# SCH_solar_powered_business_card.net
KiCad netlist of a schematic drawn in EasyEDA
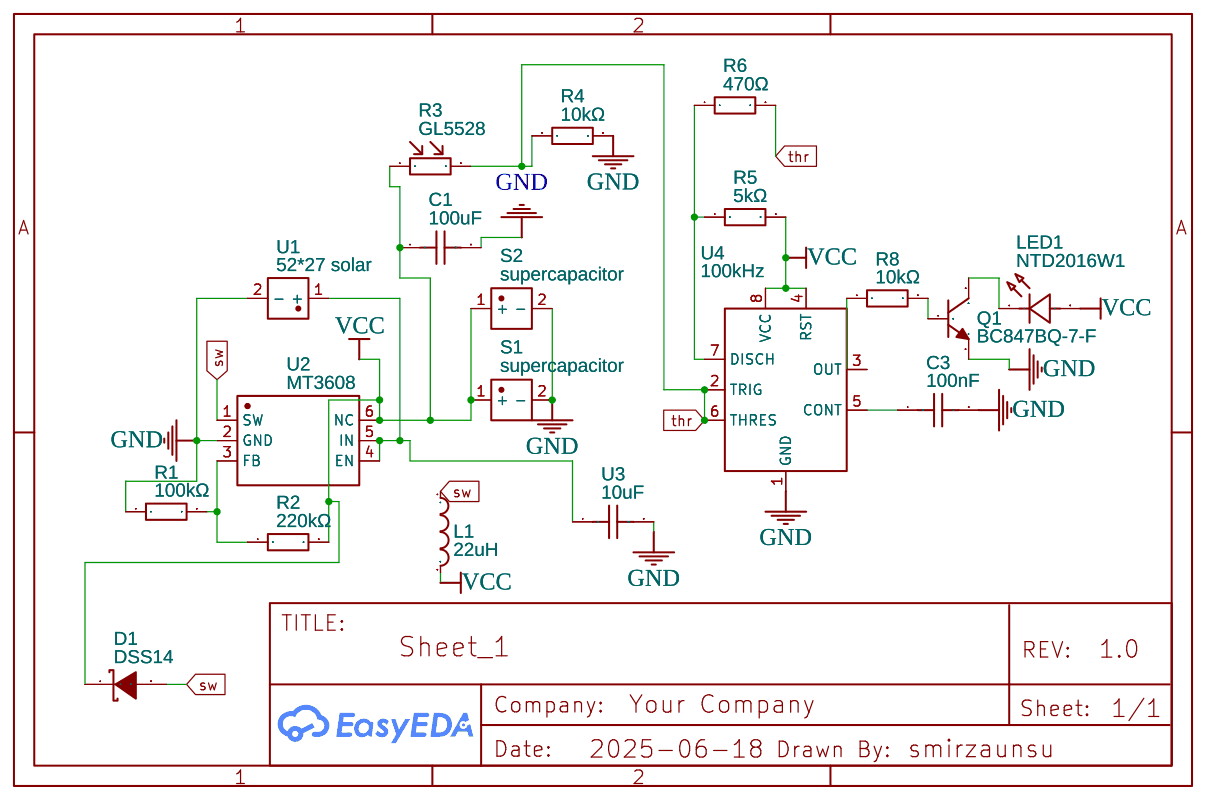
[diagram p0: schematic sheet]

(export (version "E")
  (design (tool "Eeschema 10.0.6"))
  (components
    (comp (ref "C1")
      (value "100uF")
      (fields
        (field (name "Manufacturer Part") "CGA0805X5R107M6R3MT")
        (field (name "Manufacturer") "HRE(芯声)")
      )
      (libsource (lib "") (part "CGA0805X5R107M6R3MT"))
    )
    (comp (ref "C3")
      (value "100nF")
      (fields
        (field (name "Manufacturer Part") "CGA0603X7R104K100JT")
        (field (name "Manufacturer") "HRE(芯声)")
      )
      (libsource (lib "") (part "CGA0603X7R104K100JT"))
    )
    (comp (ref "D1")
      (value "DSS14")
      (fields (field (name "Manufacturer") "星海"))
      (libsource (lib "") (part "DSS14"))
    )
    (comp (ref "L1")
      (value "22uH")
      (fields
        (field (name "Manufacturer Part") "SLD10D40S-220MTT")
        (field (name "Manufacturer") "Sunltech(韩国顺磁)")
      )
      (libsource (lib "") (part "SLD10D40S-220MTT"))
    )
    (comp (ref "LED1")
      (value "NTD2016W1")
      (fields (field (name "Manufacturer") "国星光电"))
      (libsource (lib "") (part "NTD2016W1"))
    )
    (comp (ref "Q1")
      (value "BC847BQ-7-F")
      (fields (field (name "Manufacturer") "DIODES(美台)"))
      (libsource (lib "") (part "BC847BQ-7-F"))
    )
    (comp (ref "R1")
      (value "100kΩ")
      (fields (field (name "Manufacturer Part") "RT0603DRE07100KL") (field (name "Manufacturer") "YAGEO(国巨)"))
      (libsource (lib "") (part "RT0603DRE07100KL"))
    )
    (comp (ref "R2")
      (value "220kΩ")
      (fields (field (name "Manufacturer Part") "RC0603JR-07220KL") (field (name "Manufacturer") "YAGEO(国巨)"))
      (libsource (lib "") (part "RC0603JR-07220KL"))
    )
    (comp (ref "R3")
      (value "GL5528")
      (fields (field (name "Manufacturer") "森霸"))
      (libsource (lib "") (part "GL5528"))
    )
    (comp (ref "R4")
      (value "10kΩ")
      (fields
        (field (name "Manufacturer Part") "0603WAD1002T5E")
        (field (name "Manufacturer") "UNI-ROYAL(厚声)")
      )
      (libsource (lib "") (part "0603WAD1002T5E"))
    )
    (comp (ref "R5")
      (value "5kΩ")
      (fields (field (name "Manufacturer Part") "RT0603BRE075KL") (field (name "Manufacturer") "YAGEO(国巨)"))
      (libsource (lib "") (part "RT0603BRE075KL"))
    )
    (comp (ref "R6")
      (value "470Ω")
      (fields (field (name "Manufacturer Part") "WR06X4700FTL") (field (name "Manufacturer") "Walsin(华新科)"))
      (libsource (lib "") (part "WR06X4700FTL"))
    )
    (comp (ref "R8")
      (value "10kΩ")
      (fields (field (name "Manufacturer Part") "AC0603FR-0710KL") (field (name "Manufacturer") "YAGEO(国巨)"))
      (libsource (lib "") (part "AC0603FR-0710KL"))
    )
    (comp (ref "S1") (value "supercapacitor") (libsource (lib "") (part "supercapacitor")))
    (comp (ref "S2") (value "supercapacitor") (libsource (lib "") (part "supercapacitor")))
    (comp (ref "U1") (value "52*27 solar") (libsource (lib "") (part "52*27 solar")))
    (comp (ref "U2")
      (value "MT3608")
      (fields (field (name "Manufacturer") "西安航天民芯"))
      (libsource (lib "") (part "MT3608"))
    )
    (comp (ref "U3")
      (value "10uF")
      (fields
        (field (name "Manufacturer Part") "CGA0603X5R106K100JT")
        (field (name "Manufacturer") "HRE(芯声)")
      )
      (libsource (lib "") (part "CGA0603X5R106K100JT"))
    )
    (comp (ref "U4")
      (value "100kHz")
      (fields (field (name "Manufacturer Part") "NE555DR") (field (name "Manufacturer") "TI(德州仪器)"))
      (libsource (lib "") (part "NE555DR"))
    )
  )
  (nets
    (net (code "1") (name "GND") (class "Default")
      (node (ref "C1") (pin "2") (pinfunction "2_2") (pintype "unspecified"))
      (node (ref "C3") (pin "2") (pinfunction "2_2") (pintype "unspecified"))
      (node (ref "Q1") (pin "2") (pinfunction "E_2") (pintype "input"))
      (node (ref "R1") (pin "1") (pinfunction "1_1") (pintype "unspecified"))
      (node (ref "R4") (pin "2") (pinfunction "2_2") (pintype "unspecified"))
      (node (ref "S1") (pin "2") (pinfunction "-_2") (pintype "unspecified"))
      (node (ref "S2") (pin "2") (pinfunction "-_2") (pintype "unspecified"))
      (node (ref "U1") (pin "2") (pinfunction "-_2") (pintype "unspecified"))
      (node (ref "U2") (pin "2") (pinfunction "GND_2") (pintype "unspecified"))
      (node (ref "U3") (pin "2") (pinfunction "2_2") (pintype "unspecified"))
      (node (ref "U4") (pin "1") (pinfunction "GND_1") (pintype "unspecified"))
    )
    (net (code "2") (name "Net-(LED1--)") (class "Default")
      (node (ref "LED1") (pin "1") (pinfunction "-_1") (pintype "unspecified"))
      (node (ref "Q1") (pin "3") (pinfunction "C_3") (pintype "input"))
    )
    (net (code "3") (name "Net-(Q1-B)") (class "Default")
      (node (ref "Q1") (pin "1") (pinfunction "B_1") (pintype "input"))
      (node (ref "R8") (pin "2") (pinfunction "2_2") (pintype "input"))
    )
    (net (code "4") (name "Net-(U1-+)") (class "Default")
      (node (ref "U1") (pin "1") (pinfunction "+_1") (pintype "unspecified"))
      (node (ref "U2") (pin "4") (pinfunction "EN_4") (pintype "unspecified"))
      (node (ref "U2") (pin "5") (pinfunction "IN_5") (pintype "unspecified"))
      (node (ref "U3") (pin "1") (pinfunction "1_1") (pintype "unspecified"))
    )
    (net (code "5") (name "Net-(U2-FB)") (class "Default")
      (node (ref "R1") (pin "2") (pinfunction "2_2") (pintype "unspecified"))
      (node (ref "R2") (pin "1") (pinfunction "1_1") (pintype "input"))
      (node (ref "U2") (pin "3") (pinfunction "FB_3") (pintype "unspecified"))
    )
    (net (code "6") (name "Net-(U4-CONT)") (class "Default")
      (node (ref "C3") (pin "1") (pinfunction "1_1") (pintype "unspecified"))
      (node (ref "U4") (pin "5") (pinfunction "CONT_5") (pintype "unspecified"))
    )
    (net (code "7") (name "Net-(U4-DISCH)") (class "Default")
      (node (ref "R5") (pin "1") (pinfunction "1_1") (pintype "unspecified"))
      (node (ref "R6") (pin "1") (pinfunction "1_1") (pintype "unspecified"))
      (node (ref "U4") (pin "7") (pinfunction "DISCH_7") (pintype "unspecified"))
    )
    (net (code "8") (name "Net-(U4-OUT)") (class "Default")
      (node (ref "R8") (pin "1") (pinfunction "1_1") (pintype "input"))
      (node (ref "U4") (pin "3") (pinfunction "OUT_3") (pintype "unspecified"))
    )
    (net (code "9") (name "VCC") (class "Default")
      (node (ref "C1") (pin "1") (pinfunction "1_1") (pintype "unspecified"))
      (node (ref "D1") (pin "1") (pinfunction "K_1") (pintype "unspecified"))
      (node (ref "L1") (pin "2") (pinfunction "2_2") (pintype "unspecified"))
      (node (ref "LED1") (pin "2") (pinfunction "+_2") (pintype "unspecified"))
      (node (ref "R2") (pin "2") (pinfunction "2_2") (pintype "input"))
      (node (ref "R3") (pin "1") (pinfunction "1_1") (pintype "input"))
      (node (ref "R5") (pin "2") (pinfunction "2_2") (pintype "unspecified"))
      (node (ref "S1") (pin "1") (pinfunction "+_1") (pintype "unspecified"))
      (node (ref "S2") (pin "1") (pinfunction "+_1") (pintype "unspecified"))
      (node (ref "U2") (pin "6") (pinfunction "NC_6") (pintype "unspecified"))
      (node (ref "U4") (pin "4") (pinfunction "RST_4") (pintype "unspecified"))
      (node (ref "U4") (pin "8") (pinfunction "VCC_8") (pintype "unspecified"))
    )
    (net (code "10") (name "sw") (class "Default")
      (node (ref "D1") (pin "2") (pinfunction "A_2") (pintype "unspecified"))
      (node (ref "L1") (pin "1") (pinfunction "1_1") (pintype "unspecified"))
      (node (ref "U2") (pin "1") (pinfunction "SW_1") (pintype "unspecified"))
    )
    (net (code "11") (name "thr") (class "Default")
      (node (ref "R3") (pin "2") (pinfunction "2_2") (pintype "input"))
      (node (ref "R4") (pin "1") (pinfunction "1_1") (pintype "unspecified"))
      (node (ref "R6") (pin "2") (pinfunction "2_2") (pintype "unspecified"))
      (node (ref "U4") (pin "2") (pinfunction "TRIG_2") (pintype "unspecified"))
      (node (ref "U4") (pin "6") (pinfunction "THRES_6") (pintype "unspecified"))
    )
  )
)
